# FanControl.net
KiCad netlist of a schematic drawn in Altium Designer
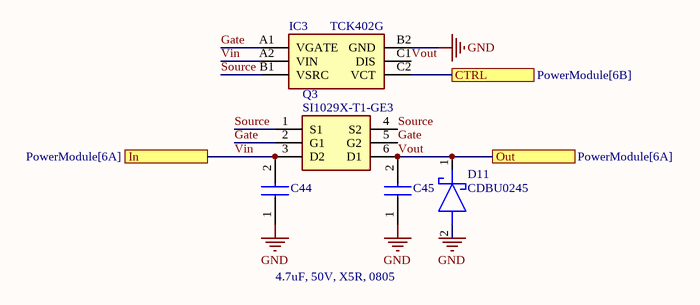
[diagram p0: FanControl.SchDoc]

(export (version "E")
  (design (tool "Eeschema 10.0.6"))
  (components
    (comp (ref "C44")
      (value "4.7uF, 50V, X5R, 0805")
      (footprint "SamacSys:CAPC2012X145N")
      (description "Capacitor")
      (fields
        (field (name "MANUFACTURER_PART_NUMBER") "GRM21BR61H475ME51L")
        (field (name "MOUSER PART NUMBER") "81-GRM21BR61H475M51L")
      )
      (libsource (lib "*") (part "GRM21BR61H475ME51L"))
    )
    (comp (ref "C45")
      (value "4.7uF, 50V, X5R, 0805")
      (footprint "SamacSys:CAPC2012X145N")
      (description "Capacitor")
      (fields
        (field (name "MANUFACTURER_PART_NUMBER") "GRM21BR61H475ME51L")
        (field (name "MOUSER PART NUMBER") "81-GRM21BR61H475M51L")
      )
      (libsource (lib "*") (part "GRM21BR61H475ME51L"))
    )
    (comp (ref "D11")
      (value "CDBU0245")
      (footprint "SamacSys:DIOC1709X85N")
      (description "Schottky Diode")
      (fields (field (name "MOUSER PART NUMBER") "750-CDBU0245"))
      (libsource (lib "*") (part "CDBU0245"))
    )
    (comp (ref "IC3")
      (value "TCK402G")
      (footprint "SamacSys:BGA6C40P2X3_80X120X59")
      (description "Integrated Circuit")
      (libsource (lib "*") (part "TCK402G"))
    )
    (comp (ref "Q3")
      (value "SI1029X-T1-GE3")
      (footprint "SamacSys:SOTFL50P160X60-6N")
      (description "Transistor")
      (fields (field (name "MOUSER PART NUMBER") "781-SI1029X-T1-GE3"))
      (libsource (lib "*") (part "SI1029X-T1-GE3"))
    )
  )
  (nets
    (net (code "1") (name "/CTRL") (class "Default")
      (node (ref "IC3") (pin "C2") (pinfunction "VCT_C2") (pintype "passive"))
    )
    (net (code "2") (name "/Gate") (class "Default")
      (node (ref "IC3") (pin "A1") (pinfunction "VGATE_A1") (pintype "passive"))
      (node (ref "Q3") (pin "2") (pinfunction "G1_2") (pintype "passive"))
      (node (ref "Q3") (pin "5") (pinfunction "G2_5") (pintype "passive"))
    )
    (net (code "3") (name "/Source") (class "Default")
      (node (ref "IC3") (pin "B1") (pinfunction "VSRC_B1") (pintype "passive"))
      (node (ref "Q3") (pin "1") (pinfunction "S1_1") (pintype "passive"))
      (node (ref "Q3") (pin "4") (pinfunction "S2_4") (pintype "passive"))
    )
    (net (code "4") (name "/Vin") (class "Default")
      (node (ref "C44") (pin "2") (pinfunction "2_2") (pintype "passive"))
      (node (ref "IC3") (pin "A2") (pinfunction "VIN_A2") (pintype "passive"))
      (node (ref "Q3") (pin "3") (pinfunction "D2_3") (pintype "passive"))
    )
    (net (code "5") (name "/Vout") (class "Default")
      (node (ref "C45") (pin "2") (pinfunction "2_2") (pintype "passive"))
      (node (ref "D11") (pin "1") (pinfunction "K_1") (pintype "passive"))
      (node (ref "IC3") (pin "C1") (pinfunction "DIS_C1") (pintype "passive"))
      (node (ref "Q3") (pin "6") (pinfunction "D1_6") (pintype "passive"))
    )
    (net (code "6") (name "GND") (class "Default")
      (node (ref "C44") (pin "1") (pinfunction "1_1") (pintype "passive"))
      (node (ref "C45") (pin "1") (pinfunction "1_1") (pintype "passive"))
      (node (ref "D11") (pin "2") (pinfunction "A_2") (pintype "passive"))
      (node (ref "IC3") (pin "B2") (pinfunction "GND_B2") (pintype "passive"))
    )
  )
)
